# STM32EVALBOARD.net
KiCad netlist of a schematic drawn in Altium Designer
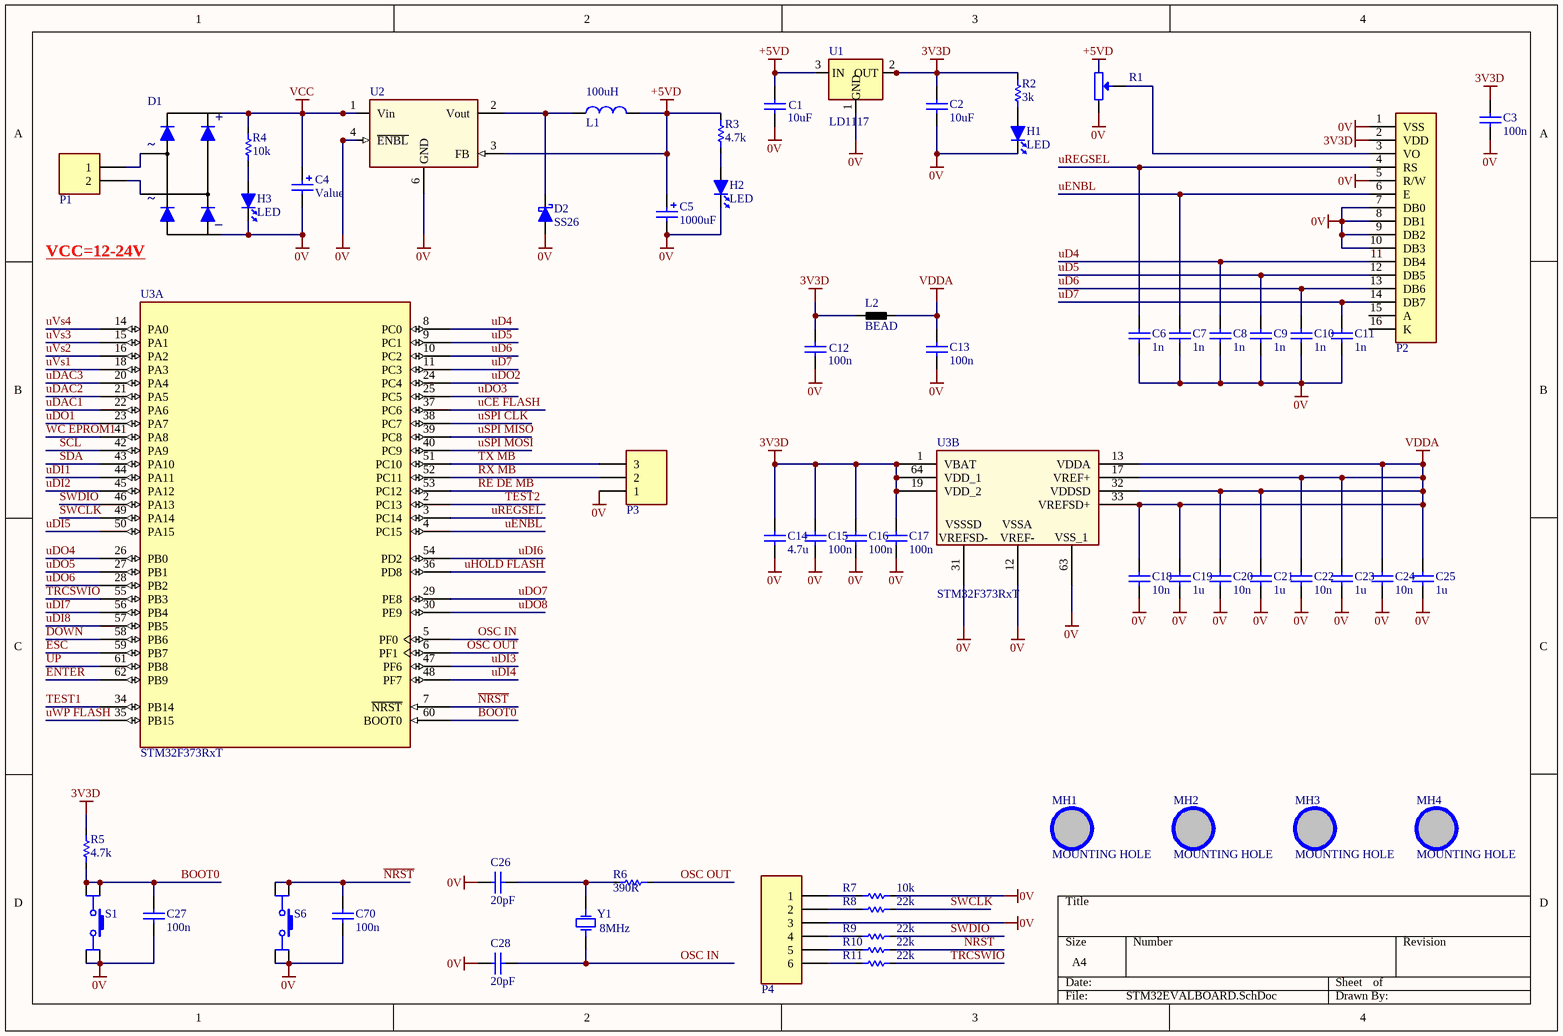
[diagram p0: STM32EVALBOARD.SchDoc]

(export (version "E")
  (design (tool "Eeschema 10.0.6"))
  (components
    (comp (ref "C1")
      (value "10uF")
      (footprint "CC3216-1206L")
      (description "Capacitor")
      (libsource (lib "SchLibrary") (part "CAPACITOR NON-POL"))
    )
    (comp (ref "C2")
      (value "10uF")
      (footprint "CC3216-1206L")
      (description "Capacitor")
      (libsource (lib "SchLibrary") (part "CAPACITOR NON-POL"))
    )
    (comp (ref "C3")
      (value "100n")
      (footprint "CC3216-1206L")
      (description "Capacitor")
      (libsource (lib "SchLibrary") (part "CAPACITOR NON-POL"))
    )
    (comp (ref "C4")
      (value "Value")
      (footprint "CAP AL-EL H12MM D8MM P3.5MM")
      (description "Capacitor")
      (libsource (lib "SchLibrary") (part "CAPACITOR POL"))
    )
    (comp (ref "C5")
      (value "1000uF")
      (footprint "CAP AL-EL H12MM D8MM P3.5MM")
      (description "Capacitor")
      (libsource (lib "SchLibrary") (part "CAPACITOR POL"))
    )
    (comp (ref "C6")
      (value "1n")
      (footprint "CC3216-1206L")
      (description "Capacitor")
      (libsource (lib "SchLibrary") (part "CAPACITOR NON-POL"))
    )
    (comp (ref "C7")
      (value "1n")
      (footprint "CC3216-1206L")
      (description "Capacitor")
      (libsource (lib "SchLibrary") (part "CAPACITOR NON-POL"))
    )
    (comp (ref "C8")
      (value "1n")
      (footprint "CC3216-1206L")
      (description "Capacitor")
      (libsource (lib "SchLibrary") (part "CAPACITOR NON-POL"))
    )
    (comp (ref "C9")
      (value "1n")
      (footprint "CC3216-1206L")
      (description "Capacitor")
      (libsource (lib "SchLibrary") (part "CAPACITOR NON-POL"))
    )
    (comp (ref "C10")
      (value "1n")
      (footprint "CC3216-1206L")
      (description "Capacitor")
      (libsource (lib "SchLibrary") (part "CAPACITOR NON-POL"))
    )
    (comp (ref "C11")
      (value "1n")
      (footprint "CC3216-1206L")
      (description "Capacitor")
      (libsource (lib "SchLibrary") (part "CAPACITOR NON-POL"))
    )
    (comp (ref "C12")
      (value "100n")
      (footprint "CC3216-1206L")
      (description "Capacitor")
      (libsource (lib "SchLibrary") (part "CAPACITOR NON-POL"))
    )
    (comp (ref "C13")
      (value "100n")
      (footprint "CC3216-1206L")
      (description "Capacitor")
      (libsource (lib "SchLibrary") (part "CAPACITOR NON-POL"))
    )
    (comp (ref "C14")
      (value "4.7u")
      (footprint "CC3216-1206L")
      (description "Capacitor")
      (libsource (lib "SchLibrary") (part "CAPACITOR NON-POL"))
    )
    (comp (ref "C15")
      (value "100n")
      (footprint "CC3216-1206L")
      (description "Capacitor")
      (libsource (lib "SchLibrary") (part "CAPACITOR NON-POL"))
    )
    (comp (ref "C16")
      (value "100n")
      (footprint "CC3216-1206L")
      (description "Capacitor")
      (libsource (lib "SchLibrary") (part "CAPACITOR NON-POL"))
    )
    (comp (ref "C17")
      (value "100n")
      (footprint "CC3216-1206L")
      (description "Capacitor")
      (libsource (lib "SchLibrary") (part "CAPACITOR NON-POL"))
    )
    (comp (ref "C18")
      (value "10n")
      (footprint "CC3216-1206L")
      (description "Capacitor")
      (libsource (lib "SchLibrary") (part "CAPACITOR NON-POL"))
    )
    (comp (ref "C19")
      (value "1u")
      (footprint "CC3216-1206L")
      (description "Capacitor")
      (libsource (lib "SchLibrary") (part "CAPACITOR NON-POL"))
    )
    (comp (ref "C20")
      (value "10n")
      (footprint "CC3216-1206L")
      (description "Capacitor")
      (libsource (lib "SchLibrary") (part "CAPACITOR NON-POL"))
    )
    (comp (ref "C21")
      (value "1u")
      (footprint "CC3216-1206L")
      (description "Capacitor")
      (libsource (lib "SchLibrary") (part "CAPACITOR NON-POL"))
    )
    (comp (ref "C22")
      (value "10n")
      (footprint "CC3216-1206L")
      (description "Capacitor")
      (libsource (lib "SchLibrary") (part "CAPACITOR NON-POL"))
    )
    (comp (ref "C23")
      (value "1u")
      (footprint "CC3216-1206L")
      (description "Capacitor")
      (libsource (lib "SchLibrary") (part "CAPACITOR NON-POL"))
    )
    (comp (ref "C24")
      (value "10n")
      (footprint "CC3216-1206L")
      (description "Capacitor")
      (libsource (lib "SchLibrary") (part "CAPACITOR NON-POL"))
    )
    (comp (ref "C25")
      (value "1u")
      (footprint "CC3216-1206L")
      (description "Capacitor")
      (libsource (lib "SchLibrary") (part "CAPACITOR NON-POL"))
    )
    (comp (ref "C26")
      (value "20pF")
      (footprint "CC3216-1206L")
      (description "Capacitor")
      (libsource (lib "SchLibrary") (part "CAPACITOR NON-POL"))
    )
    (comp (ref "C27")
      (value "100n")
      (footprint "CC3216-1206L")
      (description "Capacitor")
      (libsource (lib "SchLibrary") (part "CAPACITOR NON-POL"))
    )
    (comp (ref "C28")
      (value "20pF")
      (footprint "CC3216-1206L")
      (description "Capacitor")
      (libsource (lib "SchLibrary") (part "CAPACITOR NON-POL"))
    )
    (comp (ref "C70")
      (value "100n")
      (footprint "CC3216-1206L")
      (description "Capacitor")
      (libsource (lib "SchLibrary") (part "CAPACITOR NON-POL"))
    )
    (comp (ref "D1")
      (value "Single Phase Bridge Diode")
      (footprint "B10S_R2")
      (libsource (lib "SchLibrary") (part "DIODE DRIDGE"))
    )
    (comp (ref "D2")
      (value "SS26")
      (footprint "SMB")
      (description "SINGLE SCHOTTKY DIODE\r\nCheck the suitability of the case with the pin number")
      (libsource (lib "SchLibrary") (part "DIODE SCHOTTKY"))
    )
    (comp (ref "H1") (value "LED") (footprint "LED1206") (libsource (lib "SchLibrary") (part "LED")))
    (comp (ref "H2") (value "LED") (footprint "LED1206") (libsource (lib "SchLibrary") (part "LED")))
    (comp (ref "H3") (value "LED") (footprint "LED1206") (libsource (lib "SchLibrary") (part "LED")))
    (comp (ref "L1") (value "100uH") (footprint "FPI1005") (libsource (lib "SchLibrary") (part "INDUCTOR")))
    (comp (ref "L2")
      (value "BEAD")
      (footprint "CL3216-1206L")
      (description "FERRITE BEAD")
      (libsource (lib "SchLibrary") (part "BEAD"))
    )
    (comp (ref "MH1")
      (value "MOUNTING HOLE")
      (footprint "MOUNTING HOLE ROUND NONPLATED 3MM PLASTIC")
      (libsource (lib "SchLibrary") (part "MOUNTING HOLE"))
    )
    (comp (ref "MH2")
      (value "MOUNTING HOLE")
      (footprint "MOUNTING HOLE ROUND NONPLATED 3MM PLASTIC")
      (libsource (lib "SchLibrary") (part "MOUNTING HOLE"))
    )
    (comp (ref "MH3")
      (value "MOUNTING HOLE")
      (footprint "MOUNTING HOLE ROUND NONPLATED 3MM PLASTIC")
      (libsource (lib "SchLibrary") (part "MOUNTING HOLE"))
    )
    (comp (ref "MH4")
      (value "MOUNTING HOLE")
      (footprint "MOUNTING HOLE ROUND NONPLATED 3MM PLASTIC")
      (libsource (lib "SchLibrary") (part "MOUNTING HOLE"))
    )
    (comp (ref "P1")
      (value "CONNECTOR, 1x2, 2P")
      (footprint "DG128-5.0-02P-14")
      (libsource (lib "SchLibrary") (part "CONNECTOR, 1x2, 2P"))
    )
    (comp (ref "P2")
      (value "CONNECTOR LCD 1x16")
      (footprint "LCD1602")
      (description "LCD CONNECTOR 1x16")
      (libsource (lib "SchLibrary") (part "CONNECTOR LCD 1x16"))
    )
    (comp (ref "P3")
      (value "CONNECTOR, 1x3, 3P")
      (footprint "HDR_MALE_1X3_3P_2.54MM_180")
      (libsource (lib "SchLibrary") (part "CONNECTOR, 1x3, 3P"))
    )
    (comp (ref "P4")
      (value "CONNECTOR 1X6-6P")
      (footprint "HDR_MALE_1X6_56_2.54MM_180")
      (libsource (lib "SchLibrary") (part "CONNECTOR 1X6-6P"))
    )
    (comp (ref "R1")
      (value "Trimpot")
      (footprint "TRIMPOT 3386")
      (libsource (lib "SchLibrary") (part "Trimpot"))
    )
    (comp (ref "R2")
      (value "3k")
      (footprint "CR3216-1206l")
      (description "Resistor")
      (libsource (lib "SchLibrary") (part "RESISTOR"))
    )
    (comp (ref "R3")
      (value "4.7k")
      (footprint "CR3216-1206l")
      (description "Resistor")
      (libsource (lib "SchLibrary") (part "RESISTOR"))
    )
    (comp (ref "R4")
      (value "10k")
      (footprint "CR3216-1206l")
      (description "Resistor")
      (libsource (lib "SchLibrary") (part "RESISTOR"))
    )
    (comp (ref "R5")
      (value "4.7k")
      (footprint "CR3216-1206l")
      (description "Resistor")
      (libsource (lib "SchLibrary") (part "RESISTOR"))
    )
    (comp (ref "R6")
      (value "390R")
      (footprint "CR3216-1206l")
      (description "Resistor")
      (libsource (lib "SchLibrary") (part "RESISTOR"))
    )
    (comp (ref "R7")
      (value "10k")
      (footprint "CR3216-1206l")
      (description "Resistor")
      (libsource (lib "SchLibrary") (part "RESISTOR"))
    )
    (comp (ref "R8")
      (value "22k")
      (footprint "CR3216-1206l")
      (description "Resistor")
      (libsource (lib "SchLibrary") (part "RESISTOR"))
    )
    (comp (ref "R9")
      (value "22k")
      (footprint "CR3216-1206l")
      (description "Resistor")
      (libsource (lib "SchLibrary") (part "RESISTOR"))
    )
    (comp (ref "R10")
      (value "22k")
      (footprint "CR3216-1206l")
      (description "Resistor")
      (libsource (lib "SchLibrary") (part "RESISTOR"))
    )
    (comp (ref "R11")
      (value "22k")
      (footprint "CR3216-1206l")
      (description "Resistor")
      (libsource (lib "SchLibrary") (part "RESISTOR"))
    )
    (comp (ref "S1")
      (value "SWITCH TACT")
      (footprint "SWITCH TACTILE SMD 6x6 4.3mm")
      (description "TACT SWITCH")
      (libsource (lib "SchLibrary") (part "SWITCH TACT"))
    )
    (comp (ref "S6")
      (value "SWITCH TACT")
      (footprint "SWITCH TACTILE SMD 6x6 4.3mm")
      (description "TACT SWITCH")
      (libsource (lib "SchLibrary") (part "SWITCH TACT"))
    )
    (comp (ref "U1")
      (value "LD1117")
      (footprint "SOT230P700X180-4N")
      (description "Linear Voltage Regulators")
      (libsource (lib "SchLibrary") (part "LD1117"))
    )
    (comp (ref "U2")
      (value "IC-2576 V.REG.3A STEP DOWN SOP-8PP")
      (footprint "SOIC127P600X175-8N")
      (description "3A, 52kHz, Step-Down Switching Regulator")
      (libsource (lib "SchLibrary") (part "LM2576DP"))
    )
    (comp (ref "U3")
      (value "STM32F373RxT")
      (footprint "LQFP64")
      (libsource (lib "SchLibrary") (part "STM32F373RxT"))
    )
    (comp (ref "Y1") (value "8MHz") (footprint "HC49S SMD") (libsource (lib "SchLibrary") (part "XTAL")))
  )
  (nets
    (net (code "1") (name "+5VD") (class "Default")
      (node (ref "C1") (pin "1") (pintype "passive"))
      (node (ref "C5") (pin "1") (pinfunction "1_1") (pintype "passive"))
      (node (ref "L1") (pin "2") (pinfunction "2_2") (pintype "passive"))
      (node (ref "R1") (pin "1") (pinfunction "1_1") (pintype "passive"))
      (node (ref "R3") (pin "2") (pinfunction "2_2") (pintype "passive"))
      (node (ref "U1") (pin "3") (pinfunction "IN_3") (pintype "power_in"))
      (node (ref "U2") (pin "3") (pinfunction "FB_3") (pintype "input"))
    )
    (net (code "2") (name "/BOOT0") (class "Default")
      (node (ref "C27") (pin "1") (pintype "passive"))
      (node (ref "R5") (pin "2") (pinfunction "2_2") (pintype "passive"))
      (node (ref "S1") (pin "1") (pinfunction "A_1") (pintype "passive"))
      (node (ref "S1") (pin "2") (pinfunction "A_2") (pintype "passive"))
      (node (ref "U3") (pin "60") (pinfunction "BOOT0_60") (pintype "input"))
    )
    (net (code "3") (name "/DOWN") (class "Default")
      (node (ref "U3") (pin "58") (pinfunction "PB6_58") (pintype "bidirectional"))
    )
    (net (code "4") (name "/ENTER") (class "Default")
      (node (ref "U3") (pin "62") (pinfunction "PB9_62") (pintype "bidirectional"))
    )
    (net (code "5") (name "/ESC") (class "Default")
      (node (ref "U3") (pin "59") (pinfunction "PB7_59") (pintype "bidirectional"))
    )
    (net (code "6") (name "/OSC IN") (class "Default")
      (node (ref "C28") (pin "2") (pintype "passive"))
      (node (ref "U3") (pin "5") (pinfunction "PF0_5") (pintype "bidirectional"))
      (node (ref "Y1") (pin "1") (pinfunction "OSC1_1") (pintype "passive"))
    )
    (net (code "7") (name "/OSC OUT") (class "Default")
      (node (ref "R6") (pin "1") (pinfunction "1_1") (pintype "passive"))
      (node (ref "U3") (pin "6") (pinfunction "PF1_6") (pintype "bidirectional"))
    )
    (net (code "8") (name "/RX MB") (class "Default")
      (node (ref "P3") (pin "2") (pinfunction "2_2") (pintype "passive"))
      (node (ref "U3") (pin "52") (pinfunction "PC11_52") (pintype "bidirectional"))
    )
    (net (code "9") (name "/SCL") (class "Default")
      (node (ref "U3") (pin "42") (pinfunction "PA9_42") (pintype "bidirectional"))
    )
    (net (code "10") (name "/SDA") (class "Default")
      (node (ref "U3") (pin "43") (pinfunction "PA10_43") (pintype "bidirectional"))
    )
    (net (code "11") (name "/SWCLK") (class "Default")
      (node (ref "R8") (pin "1") (pinfunction "1_1") (pintype "passive"))
      (node (ref "U3") (pin "49") (pinfunction "PA14_49") (pintype "bidirectional"))
    )
    (net (code "12") (name "/SWDIO") (class "Default")
      (node (ref "R9") (pin "1") (pinfunction "1_1") (pintype "passive"))
      (node (ref "U3") (pin "46") (pinfunction "PA13_46") (pintype "bidirectional"))
    )
    (net (code "13") (name "/TEST1") (class "Default")
      (node (ref "U3") (pin "34") (pinfunction "PB14_34") (pintype "bidirectional"))
    )
    (net (code "14") (name "/TEST2") (class "Default")
      (node (ref "U3") (pin "2") (pinfunction "PC13_2") (pintype "bidirectional"))
    )
    (net (code "15") (name "/TRCSWIO") (class "Default")
      (node (ref "R11") (pin "1") (pinfunction "1_1") (pintype "passive"))
      (node (ref "U3") (pin "55") (pinfunction "PB3_55") (pintype "bidirectional"))
    )
    (net (code "16") (name "/TX MB") (class "Default")
      (node (ref "P3") (pin "3") (pinfunction "3_3") (pintype "passive"))
      (node (ref "U3") (pin "51") (pinfunction "PC10_51") (pintype "bidirectional"))
    )
    (net (code "17") (name "/UP") (class "Default")
      (node (ref "U3") (pin "61") (pinfunction "PB8_61") (pintype "bidirectional"))
    )
    (net (code "18") (name "/uCE FLASH") (class "Default")
      (node (ref "U3") (pin "37") (pinfunction "PC6_37") (pintype "bidirectional"))
    )
    (net (code "19") (name "/uD4") (class "Default")
      (node (ref "C8") (pin "1") (pintype "passive"))
      (node (ref "P2") (pin "11") (pinfunction "DB4_11") (pintype "passive"))
      (node (ref "U3") (pin "8") (pinfunction "PC0_8") (pintype "bidirectional"))
    )
    (net (code "20") (name "/uD5") (class "Default")
      (node (ref "C9") (pin "1") (pintype "passive"))
      (node (ref "P2") (pin "12") (pinfunction "DB5_12") (pintype "passive"))
      (node (ref "U3") (pin "9") (pinfunction "PC1_9") (pintype "bidirectional"))
    )
    (net (code "21") (name "/uD6") (class "Default")
      (node (ref "C10") (pin "1") (pintype "passive"))
      (node (ref "P2") (pin "13") (pinfunction "DB6_13") (pintype "passive"))
      (node (ref "U3") (pin "10") (pinfunction "PC2_10") (pintype "bidirectional"))
    )
    (net (code "22") (name "/uD7") (class "Default")
      (node (ref "C11") (pin "1") (pintype "passive"))
      (node (ref "P2") (pin "14") (pinfunction "DB7_14") (pintype "passive"))
      (node (ref "U3") (pin "11") (pinfunction "PC3_11") (pintype "bidirectional"))
    )
    (net (code "23") (name "/uDAC1") (class "Default")
      (node (ref "U3") (pin "22") (pinfunction "PA6_22") (pintype "bidirectional"))
    )
    (net (code "24") (name "/uDAC2") (class "Default")
      (node (ref "U3") (pin "21") (pinfunction "PA5_21") (pintype "bidirectional"))
    )
    (net (code "25") (name "/uDAC3") (class "Default")
      (node (ref "U3") (pin "20") (pinfunction "PA4_20") (pintype "bidirectional"))
    )
    (net (code "26") (name "/uDI1") (class "Default")
      (node (ref "U3") (pin "44") (pinfunction "PA11_44") (pintype "bidirectional"))
    )
    (net (code "27") (name "/uDI2") (class "Default")
      (node (ref "U3") (pin "45") (pinfunction "PA12_45") (pintype "bidirectional"))
    )
    (net (code "28") (name "/uDI3") (class "Default")
      (node (ref "U3") (pin "47") (pinfunction "PF6_47") (pintype "bidirectional"))
    )
    (net (code "29") (name "/uDI4") (class "Default")
      (node (ref "U3") (pin "48") (pinfunction "PF7_48") (pintype "bidirectional"))
    )
    (net (code "30") (name "/uDI5") (class "Default")
      (node (ref "U3") (pin "50") (pinfunction "PA15_50") (pintype "bidirectional"))
    )
    (net (code "31") (name "/uDI6") (class "Default")
      (node (ref "U3") (pin "54") (pinfunction "PD2_54") (pintype "bidirectional"))
    )
    (net (code "32") (name "/uDI7") (class "Default")
      (node (ref "U3") (pin "56") (pinfunction "PB4_56") (pintype "bidirectional"))
    )
    (net (code "33") (name "/uDI8") (class "Default")
      (node (ref "U3") (pin "57") (pinfunction "PB5_57") (pintype "bidirectional"))
    )
    (net (code "34") (name "/uDO1") (class "Default")
      (node (ref "U3") (pin "23") (pinfunction "PA7_23") (pintype "bidirectional"))
    )
    (net (code "35") (name "/uDO2") (class "Default")
      (node (ref "U3") (pin "24") (pinfunction "PC4_24") (pintype "bidirectional"))
    )
    (net (code "36") (name "/uDO3") (class "Default")
      (node (ref "U3") (pin "25") (pinfunction "PC5_25") (pintype "bidirectional"))
    )
    (net (code "37") (name "/uDO4") (class "Default")
      (node (ref "U3") (pin "26") (pinfunction "PB0_26") (pintype "bidirectional"))
    )
    (net (code "38") (name "/uDO5") (class "Default")
      (node (ref "U3") (pin "27") (pinfunction "PB1_27") (pintype "bidirectional"))
    )
    (net (code "39") (name "/uDO6") (class "Default")
      (node (ref "U3") (pin "28") (pinfunction "PB2_28") (pintype "bidirectional"))
    )
    (net (code "40") (name "/uDO7") (class "Default")
      (node (ref "U3") (pin "29") (pinfunction "PE8_29") (pintype "bidirectional"))
    )
    (net (code "41") (name "/uDO8") (class "Default")
      (node (ref "U3") (pin "30") (pinfunction "PE9_30") (pintype "bidirectional"))
    )
    (net (code "42") (name "/uENBL") (class "Default")
      (node (ref "C7") (pin "1") (pintype "passive"))
      (node (ref "P2") (pin "6") (pinfunction "E_6") (pintype "passive"))
      (node (ref "U3") (pin "4") (pinfunction "PC15_4") (pintype "bidirectional"))
    )
    (net (code "43") (name "/uHOLD FLASH") (class "Default")
      (node (ref "U3") (pin "36") (pinfunction "PD8_36") (pintype "bidirectional"))
    )
    (net (code "44") (name "/uREGSEL") (class "Default")
      (node (ref "C6") (pin "1") (pintype "passive"))
      (node (ref "P2") (pin "4") (pinfunction "RS_4") (pintype "passive"))
      (node (ref "U3") (pin "3") (pinfunction "PC14_3") (pintype "bidirectional"))
    )
    (net (code "45") (name "/uSPI CLK") (class "Default")
      (node (ref "U3") (pin "38") (pinfunction "PC7_38") (pintype "bidirectional"))
    )
    (net (code "46") (name "/uSPI MISO") (class "Default")
      (node (ref "U3") (pin "39") (pinfunction "PC8_39") (pintype "bidirectional"))
    )
    (net (code "47") (name "/uSPI MOSI") (class "Default")
      (node (ref "U3") (pin "40") (pinfunction "PC9_40") (pintype "bidirectional"))
    )
    (net (code "48") (name "/uVs1") (class "Default")
      (node (ref "U3") (pin "18") (pinfunction "PA3_18") (pintype "bidirectional"))
    )
    (net (code "49") (name "/uVs2") (class "Default")
      (node (ref "U3") (pin "16") (pinfunction "PA2_16") (pintype "bidirectional"))
    )
    (net (code "50") (name "/uVs3") (class "Default")
      (node (ref "U3") (pin "15") (pinfunction "PA1_15") (pintype "bidirectional"))
    )
    (net (code "51") (name "/uVs4") (class "Default")
      (node (ref "U3") (pin "14") (pinfunction "PA0_14") (pintype "bidirectional"))
    )
    (net (code "52") (name "/uWP FLASH") (class "Default")
      (node (ref "U3") (pin "35") (pinfunction "PB15_35") (pintype "bidirectional"))
    )
    (net (code "53") (name "/~{NRST}") (class "Default")
      (node (ref "C70") (pin "1") (pintype "passive"))
      (node (ref "R10") (pin "1") (pinfunction "1_1") (pintype "passive"))
      (node (ref "S6") (pin "1") (pinfunction "A_1") (pintype "passive"))
      (node (ref "S6") (pin "2") (pinfunction "A_2") (pintype "passive"))
      (node (ref "U3") (pin "7") (pinfunction "~{NRST}_7") (pintype "input"))
    )
    (net (code "54") (name "/~{RE} DE MB") (class "Default")
      (node (ref "U3") (pin "53") (pinfunction "PC12_53") (pintype "bidirectional"))
    )
    (net (code "55") (name "/~{WC} EPROM1") (class "Default")
      (node (ref "U3") (pin "41") (pinfunction "PA8_41") (pintype "bidirectional"))
    )
    (net (code "56") (name "0V") (class "Default")
      (node (ref "C1") (pin "2") (pintype "passive"))
      (node (ref "C10") (pin "2") (pintype "passive"))
      (node (ref "C11") (pin "2") (pintype "passive"))
      (node (ref "C12") (pin "2") (pintype "passive"))
      (node (ref "C13") (pin "2") (pintype "passive"))
      (node (ref "C14") (pin "2") (pintype "passive"))
      (node (ref "C15") (pin "2") (pintype "passive"))
      (node (ref "C16") (pin "2") (pintype "passive"))
      (node (ref "C17") (pin "2") (pintype "passive"))
      (node (ref "C18") (pin "2") (pintype "passive"))
      (node (ref "C19") (pin "2") (pintype "passive"))
      (node (ref "C2") (pin "2") (pintype "passive"))
      (node (ref "C20") (pin "2") (pintype "passive"))
      (node (ref "C21") (pin "2") (pintype "passive"))
      (node (ref "C22") (pin "2") (pintype "passive"))
      (node (ref "C23") (pin "2") (pintype "passive"))
      (node (ref "C24") (pin "2") (pintype "passive"))
      (node (ref "C25") (pin "2") (pintype "passive"))
      (node (ref "C26") (pin "1") (pintype "passive"))
      (node (ref "C27") (pin "2") (pintype "passive"))
      (node (ref "C28") (pin "1") (pintype "passive"))
      (node (ref "C3") (pin "2") (pintype "passive"))
      (node (ref "C4") (pin "2") (pinfunction "2_2") (pintype "passive"))
      (node (ref "C5") (pin "2") (pinfunction "2_2") (pintype "passive"))
      (node (ref "C6") (pin "2") (pintype "passive"))
      (node (ref "C7") (pin "2") (pintype "passive"))
      (node (ref "C70") (pin "2") (pintype "passive"))
      (node (ref "C8") (pin "2") (pintype "passive"))
      (node (ref "C9") (pin "2") (pintype "passive"))
      (node (ref "D1") (pin "4") (pinfunction "-_4") (pintype "passive"))
      (node (ref "D2") (pin "1") (pinfunction "1_1") (pintype "passive"))
      (node (ref "H1") (pin "2") (pinfunction "CATHODE_2") (pintype "passive"))
      (node (ref "H2") (pin "2") (pinfunction "CATHODE_2") (pintype "passive"))
      (node (ref "H3") (pin "2") (pinfunction "CATHODE_2") (pintype "passive"))
      (node (ref "P2") (pin "1") (pinfunction "VSS_1") (pintype "passive"))
      (node (ref "P2") (pin "10") (pinfunction "DB3_10") (pintype "passive"))
      (node (ref "P2") (pin "5") (pinfunction "R/W_5") (pintype "passive"))
      (node (ref "P2") (pin "7") (pinfunction "DB0_7") (pintype "passive"))
      (node (ref "P2") (pin "8") (pinfunction "DB1_8") (pintype "passive"))
      (node (ref "P2") (pin "9") (pinfunction "DB2_9") (pintype "passive"))
      (node (ref "P3") (pin "1") (pinfunction "1_1") (pintype "passive"))
      (node (ref "P4") (pin "3") (pinfunction "3_3") (pintype "passive"))
      (node (ref "R1") (pin "3") (pinfunction "3_3") (pintype "passive"))
      (node (ref "R7") (pin "1") (pinfunction "1_1") (pintype "passive"))
      (node (ref "S1") (pin "3") (pinfunction "B_3") (pintype "passive"))
      (node (ref "S1") (pin "4") (pinfunction "B_4") (pintype "passive"))
      (node (ref "S6") (pin "3") (pinfunction "B_3") (pintype "passive"))
      (node (ref "S6") (pin "4") (pinfunction "B_4") (pintype "passive"))
      (node (ref "U1") (pin "1") (pinfunction "GND_1") (pintype "power_in"))
      (node (ref "U2") (pin "4") (pinfunction "~{ENBL}_4") (pintype "input"))
      (node (ref "U2") (pin "6") (pinfunction "GND_6") (pintype "power_in"))
      (node (ref "U3") (pin "12") (pinfunction "VSSA/VREF-_12") (pintype "power_in"))
      (node (ref "U3") (pin "31") (pinfunction "VSSSD/VREFSD-_31") (pintype "power_in"))
      (node (ref "U3") (pin "63") (pinfunction "VSS_1_63") (pintype "power_in"))
    )
    (net (code "57") (name "3V3D") (class "Default")
      (node (ref "C12") (pin "1") (pintype "passive"))
      (node (ref "C14") (pin "1") (pintype "passive"))
      (node (ref "C15") (pin "1") (pintype "passive"))
      (node (ref "C16") (pin "1") (pintype "passive"))
      (node (ref "C17") (pin "1") (pintype "passive"))
      (node (ref "C2") (pin "1") (pintype "passive"))
      (node (ref "C3") (pin "1") (pintype "passive"))
      (node (ref "L2") (pin "2") (pinfunction "2_2") (pintype "passive"))
      (node (ref "P2") (pin "2") (pinfunction "VDD_2") (pintype "passive"))
      (node (ref "R2") (pin "2") (pinfunction "2_2") (pintype "passive"))
      (node (ref "R5") (pin "1") (pinfunction "1_1") (pintype "passive"))
      (node (ref "U1") (pin "2") (pinfunction "OUT_2") (pintype "power_in"))
      (node (ref "U1") (pin "4") (pinfunction "OUT_4") (pintype "power_in"))
      (node (ref "U3") (pin "1") (pinfunction "VBAT_1") (pintype "power_in"))
      (node (ref "U3") (pin "19") (pinfunction "VDD_2_19") (pintype "power_in"))
      (node (ref "U3") (pin "64") (pinfunction "VDD_1_64") (pintype "power_in"))
    )
    (net (code "58") (name "Net-(D1-~-Pad2)") (class "Default")
      (node (ref "D1") (pin "2") (pinfunction "~_2") (pintype "passive"))
      (node (ref "P1") (pin "1") (pinfunction "1_1") (pintype "passive"))
    )
    (net (code "59") (name "Net-(D1-~-Pad3)") (class "Default")
      (node (ref "D1") (pin "3") (pinfunction "~_3") (pintype "passive"))
      (node (ref "P1") (pin "2") (pinfunction "2_2") (pintype "passive"))
    )
    (net (code "60") (name "Net-(H1-ANODE)") (class "Default")
      (node (ref "H1") (pin "1") (pinfunction "ANODE_1") (pintype "passive"))
      (node (ref "R2") (pin "1") (pinfunction "1_1") (pintype "passive"))
    )
    (net (code "61") (name "Net-(H2-ANODE)") (class "Default")
      (node (ref "H2") (pin "1") (pinfunction "ANODE_1") (pintype "passive"))
      (node (ref "R3") (pin "1") (pinfunction "1_1") (pintype "passive"))
    )
    (net (code "62") (name "Net-(H3-ANODE)") (class "Default")
      (node (ref "H3") (pin "1") (pinfunction "ANODE_1") (pintype "passive"))
      (node (ref "R4") (pin "1") (pinfunction "1_1") (pintype "passive"))
    )
    (net (code "63") (name "Net-(P2-VO)") (class "Default")
      (node (ref "P2") (pin "3") (pinfunction "VO_3") (pintype "passive"))
      (node (ref "R1") (pin "2") (pinfunction "2_2") (pintype "passive"))
    )
    (net (code "64") (name "Net-(P4-Pad1)") (class "Default")
      (node (ref "P4") (pin "1") (pinfunction "1_1") (pintype "passive"))
      (node (ref "R7") (pin "2") (pinfunction "2_2") (pintype "passive"))
    )
    (net (code "65") (name "Net-(P4-Pad2)") (class "Default")
      (node (ref "P4") (pin "2") (pinfunction "2_2") (pintype "passive"))
      (node (ref "R8") (pin "2") (pinfunction "2_2") (pintype "passive"))
    )
    (net (code "66") (name "Net-(P4-Pad4)") (class "Default")
      (node (ref "P4") (pin "4") (pinfunction "4_4") (pintype "passive"))
      (node (ref "R9") (pin "2") (pinfunction "2_2") (pintype "passive"))
    )
    (net (code "67") (name "Net-(P4-Pad5)") (class "Default")
      (node (ref "P4") (pin "5") (pinfunction "5_5") (pintype "passive"))
      (node (ref "R10") (pin "2") (pinfunction "2_2") (pintype "passive"))
    )
    (net (code "68") (name "Net-(P4-Pad6)") (class "Default")
      (node (ref "P4") (pin "6") (pinfunction "6_6") (pintype "passive"))
      (node (ref "R11") (pin "2") (pinfunction "2_2") (pintype "passive"))
    )
    (net (code "69") (name "Net-(U2-Vout)") (class "Default")
      (node (ref "D2") (pin "2") (pinfunction "2_2") (pintype "passive"))
      (node (ref "L1") (pin "1") (pinfunction "1_1") (pintype "passive"))
      (node (ref "U2") (pin "2") (pinfunction "Vout_2") (pintype "power_in"))
    )
    (net (code "70") (name "Net-(Y1-OSC2)") (class "Default")
      (node (ref "C26") (pin "2") (pintype "passive"))
      (node (ref "R6") (pin "2") (pinfunction "2_2") (pintype "passive"))
      (node (ref "Y1") (pin "2") (pinfunction "OSC2_2") (pintype "passive"))
    )
    (net (code "71") (name "VCC") (class "Default")
      (node (ref "C4") (pin "1") (pinfunction "1_1") (pintype "passive"))
      (node (ref "D1") (pin "1") (pinfunction "+_1") (pintype "passive"))
      (node (ref "R4") (pin "2") (pinfunction "2_2") (pintype "passive"))
      (node (ref "U2") (pin "1") (pinfunction "Vin_1") (pintype "power_in"))
    )
    (net (code "72") (name "VDDA") (class "Default")
      (node (ref "C13") (pin "1") (pintype "passive"))
      (node (ref "C18") (pin "1") (pintype "passive"))
      (node (ref "C19") (pin "1") (pintype "passive"))
      (node (ref "C20") (pin "1") (pintype "passive"))
      (node (ref "C21") (pin "1") (pintype "passive"))
      (node (ref "C22") (pin "1") (pintype "passive"))
      (node (ref "C23") (pin "1") (pintype "passive"))
      (node (ref "C24") (pin "1") (pintype "passive"))
      (node (ref "C25") (pin "1") (pintype "passive"))
      (node (ref "L2") (pin "1") (pinfunction "1_1") (pintype "passive"))
      (node (ref "U3") (pin "13") (pinfunction "VDDA_13") (pintype "power_in"))
      (node (ref "U3") (pin "17") (pinfunction "VREF+_17") (pintype "power_in"))
      (node (ref "U3") (pin "32") (pinfunction "VDDSD_32") (pintype "power_in"))
      (node (ref "U3") (pin "33") (pinfunction "VREFSD+_33") (pintype "power_in"))
    )
    (net (code "73") (name "unconnected-(P2-A-Pad15)") (class "Default")
      (node (ref "P2") (pin "15") (pinfunction "A_15") (pintype "passive"))
    )
    (net (code "74") (name "unconnected-(P2-K-Pad16)") (class "Default")
      (node (ref "P2") (pin "16") (pinfunction "K_16") (pintype "passive"))
    )
    (net (code "75") (name "unconnected-(U2-NC-Pad5)") (class "Default")
      (node (ref "U2") (pin "5") (pinfunction "NC_5") (pintype "passive"))
    )
    (net (code "76") (name "unconnected-(U2-NC-Pad7)") (class "Default")
      (node (ref "U2") (pin "7") (pinfunction "NC_7") (pintype "passive"))
    )
    (net (code "77") (name "unconnected-(U2-NC-Pad8)") (class "Default")
      (node (ref "U2") (pin "8") (pinfunction "NC_8") (pintype "passive"))
    )
  )
)
